# temp_filt.net
KiCad netlist of a schematic drawn in Altium Designer
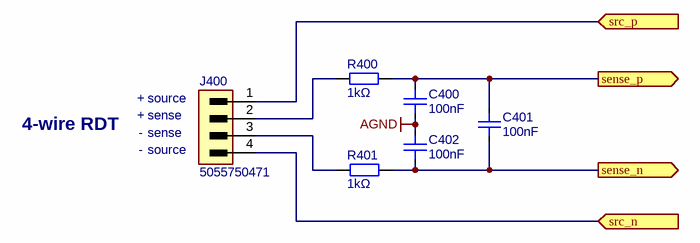
[diagram p0: temp_filt.SchDoc]

(export (version "E")
  (design (tool "Eeschema 10.0.6"))
  (components
    (comp (ref "C400")
      (value "100nF")
      (footprint "SMD0603CAP")
      (description "Ceramic Capacitor")
      (libsource (lib "SL-Library") (part "Capacitor Ceramic"))
    )
    (comp (ref "C401")
      (value "100nF")
      (footprint "SMD0603CAP")
      (description "Ceramic Capacitor")
      (libsource (lib "SL-Library") (part "Capacitor Ceramic"))
    )
    (comp (ref "C402")
      (value "100nF")
      (footprint "SMD0603CAP")
      (description "Ceramic Capacitor")
      (libsource (lib "SL-Library") (part "Capacitor Ceramic"))
    )
    (comp (ref "J400")
      (value "5055750471")
      (footprint "5055750471")
      (description "Connector 4x1P")
      (libsource (lib "SL-Library") (part "Connector 4x1P"))
    )
    (comp (ref "R400")
      (value "1kΩ")
      (footprint "SMD0603RES")
      (description "Resistor")
      (libsource (lib "SL-Library") (part "Resistor"))
    )
    (comp (ref "R401")
      (value "1kΩ")
      (footprint "SMD0603RES")
      (description "Resistor")
      (libsource (lib "SL-Library") (part "Resistor"))
    )
  )
  (nets
    (net (code "1") (name "/sense_n") (class "Default")
      (node (ref "C401") (pin "2") (pinfunction "2_2") (pintype "passive"))
      (node (ref "C402") (pin "2") (pinfunction "2_2") (pintype "passive"))
      (node (ref "R401") (pin "1") (pinfunction "1_1") (pintype "passive"))
    )
    (net (code "2") (name "/sense_p") (class "Default")
      (node (ref "C400") (pin "1") (pinfunction "1_1") (pintype "passive"))
      (node (ref "C401") (pin "1") (pinfunction "1_1") (pintype "passive"))
      (node (ref "R400") (pin "1") (pinfunction "1_1") (pintype "passive"))
    )
    (net (code "3") (name "/src_n") (class "Default")
      (node (ref "J400") (pin "4") (pinfunction "4_4") (pintype "passive"))
    )
    (net (code "4") (name "/src_p") (class "Default")
      (node (ref "J400") (pin "1") (pinfunction "1_1") (pintype "passive"))
    )
    (net (code "5") (name "AGND") (class "Default")
      (node (ref "C400") (pin "2") (pinfunction "2_2") (pintype "passive"))
      (node (ref "C402") (pin "1") (pinfunction "1_1") (pintype "passive"))
    )
    (net (code "6") (name "Net-(J400-Pad2)") (class "Default")
      (node (ref "J400") (pin "2") (pinfunction "2_2") (pintype "passive"))
      (node (ref "R400") (pin "2") (pinfunction "2_2") (pintype "passive"))
    )
    (net (code "7") (name "Net-(J400-Pad3)") (class "Default")
      (node (ref "J400") (pin "3") (pinfunction "3_3") (pintype "passive"))
      (node (ref "R401") (pin "2") (pinfunction "2_2") (pintype "passive"))
    )
  )
)
